# IMU_REV_D_1.net
KiCad netlist of a schematic drawn in Altium Designer
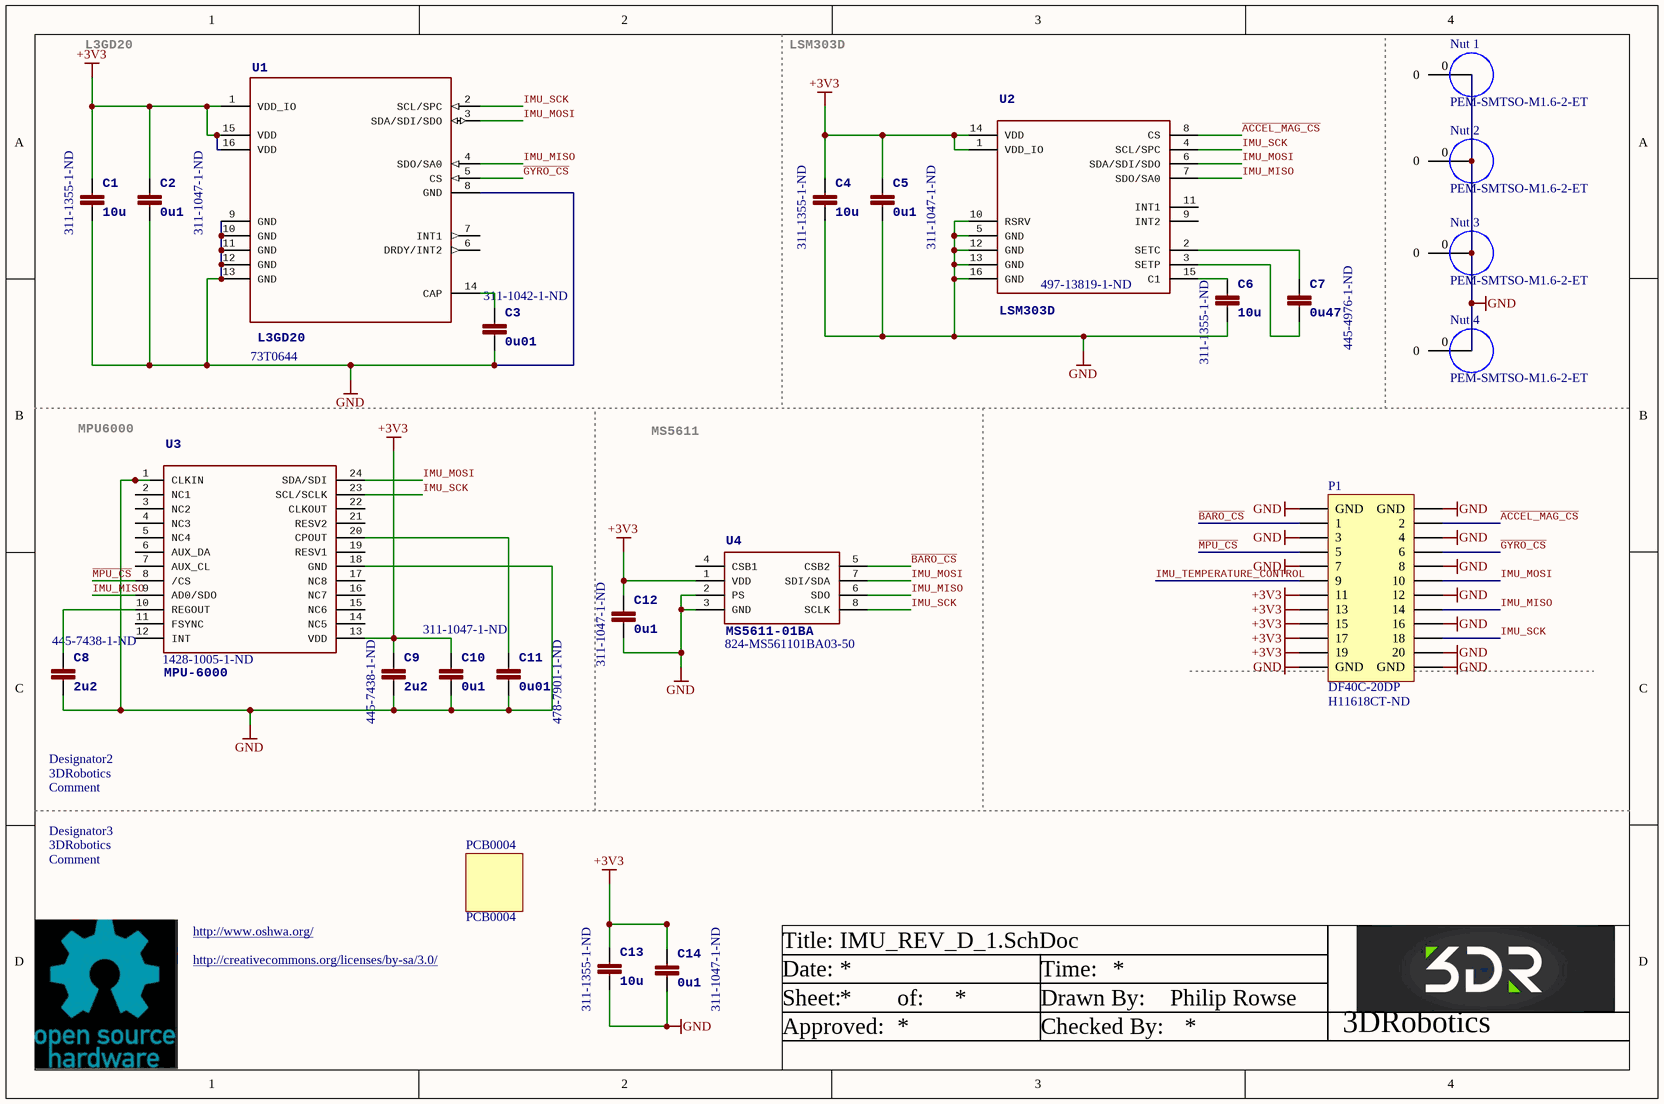
[diagram p0: IMU_REV_D_1.SchDoc]

(export (version "E")
  (design (tool "Eeschema 10.0.6"))
  (components
    (comp (ref "C1")
      (value "10u")
      (footprint "0805-CAP")
      (description "Capacitor, 10uF, 10V, Y5V, 0805, Ceramic")
      (fields
        (field (name "PARTNO") "CC0805ZKY5V6BB106")
        (field (name "SUPPLIER PART NUMBER 1") "311-1355-1-ND")
        (field (name "3DR_PARTNO") "ECM0713")
      )
      (libsource (lib "lib_pixhawk") (part "CAPACITOR-0805"))
    )
    (comp (ref "C2")
      (value "0u1")
      (footprint "0402-CAP")
      (description "Capacitor, 0.1uF, 16V, Y5V, 0402, Ceramic")
      (fields
        (field (name "PARTNO") "CC0402ZRY5V7BB104")
        (field (name "SUPPLIER PART NUMBER 1") "311-1047-1-ND")
        (field (name "3DR_PARTNO") "ECM0700")
      )
      (libsource (lib "lib_pixhawk") (part "CAPACITOR-0402"))
    )
    (comp (ref "C3")
      (value "0u01")
      (footprint "0402-CAP")
      (description "Capacitor, 10000pF, 16V, 10%, X7R, 0402, Ceramic")
      (fields
        (field (name "PARTNO") "CC0402KRX7R7BB103")
        (field (name "SUPPLIER PART NUMBER 1") "311-1042-1-ND")
        (field (name "3DR_PARTNO") "ECM0711")
      )
      (libsource (lib "lib_pixhawk") (part "CAPACITOR-0402"))
    )
    (comp (ref "C4")
      (value "10u")
      (footprint "0805-CAP")
      (description "Capacitor, 10uF, 10V, Y5V, 0805, Ceramic")
      (fields
        (field (name "PARTNO") "CC0805ZKY5V6BB106")
        (field (name "SUPPLIER PART NUMBER 1") "311-1355-1-ND")
        (field (name "3DR_PARTNO") "ECM0713")
      )
      (libsource (lib "lib_pixhawk") (part "CAPACITOR-0805"))
    )
    (comp (ref "C5")
      (value "0u1")
      (footprint "0402-CAP")
      (description "Capacitor, 0.1uF, 16V, Y5V, 0402, Ceramic")
      (fields
        (field (name "PARTNO") "CC0402ZRY5V7BB104")
        (field (name "SUPPLIER PART NUMBER 1") "311-1047-1-ND")
        (field (name "3DR_PARTNO") "ECM0700")
      )
      (libsource (lib "lib_pixhawk") (part "CAPACITOR-0402"))
    )
    (comp (ref "C6")
      (value "10u")
      (footprint "0805-CAP")
      (description "Capacitor, 10uF, 10V, Y5V, 0805, Ceramic")
      (fields
        (field (name "PARTNO") "CC0805ZKY5V6BB106")
        (field (name "SUPPLIER PART NUMBER 1") "311-1355-1-ND")
        (field (name "3DR_PARTNO") "ECM0713")
      )
      (libsource (lib "lib_pixhawk") (part "CAPACITOR-0805"))
    )
    (comp (ref "C7")
      (value "0u47")
      (footprint "0402-CAP")
      (description "Capacitor,  0.47uF, 16V, 10%, X5R, 0402, Ceramic")
      (fields
        (field (name "PARTNO") "C1005X5R1C474K050BC")
        (field (name "SUPPLIER PART NUMBER 1") "445-4976-1-ND")
        (field (name "3DR_PARTNO") "ECM0704")
      )
      (libsource (lib "lib_pixhawk") (part "CAPACITOR-0402"))
    )
    (comp (ref "C8")
      (value "2u2")
      (footprint "0603-CAP")
      (description "Capacitor, 2.2uF, 16V, 10%, X6S, 0603, Ceramic")
      (fields
        (field (name "PARTNO") "C1608X6S1C225K080AC")
        (field (name "SUPPLIER PART NUMBER 1") "445-7438-1-ND")
        (field (name "3DR_PARTNO") "ECM0619")
      )
      (libsource (lib "lib_pixhawk") (part "CAPACITOR-0603"))
    )
    (comp (ref "C9")
      (value "2u2")
      (footprint "0603-CAP")
      (description "Capacitor, 2.2uF, 16V, 10%, X6S, 0603, Ceramic")
      (fields
        (field (name "PARTNO") "C1608X6S1C225K080AC")
        (field (name "SUPPLIER PART NUMBER 1") "445-7438-1-ND")
        (field (name "3DR_PARTNO") "ECM0619")
      )
      (libsource (lib "lib_pixhawk") (part "CAPACITOR-0603"))
    )
    (comp (ref "C10")
      (value "0u1")
      (footprint "0402-CAP")
      (description "Capacitor, 0.1uF, 16V, Y5V, 0402, Ceramic")
      (fields
        (field (name "PARTNO") "CC0402ZRY5V7BB104")
        (field (name "SUPPLIER PART NUMBER 1") "311-1047-1-ND")
        (field (name "3DR_PARTNO") "ECM0700")
      )
      (libsource (lib "lib_pixhawk") (part "CAPACITOR-0402"))
    )
    (comp (ref "C11")
      (value "0u01")
      (footprint "0603-CAP")
      (description "Capacitor, 10000pF, 25V, 5%, X7R, 0603, Ceramic")
      (fields
        (field (name "PARTNO") "06033C103JAT2A")
        (field (name "SUPPLIER PART NUMBER 1") "478-7901-1-ND")
        (field (name "3DR_PARTNO") "ECM0620")
      )
      (libsource (lib "lib_pixhawk") (part "CAPACITOR-0603"))
    )
    (comp (ref "C12")
      (value "0u1")
      (footprint "0402-CAP")
      (description "Capacitor, 0.1uF, 16V, Y5V, 0402, Ceramic")
      (fields
        (field (name "PARTNO") "CC0402ZRY5V7BB104")
        (field (name "SUPPLIER PART NUMBER 1") "311-1047-1-ND")
        (field (name "3DR_PARTNO") "ECM0700")
      )
      (libsource (lib "lib_pixhawk") (part "CAPACITOR-0402"))
    )
    (comp (ref "C13")
      (value "10u")
      (footprint "0805-CAP")
      (description "Capacitor, 10uF, 10V, Y5V, 0805, Ceramic")
      (fields
        (field (name "PARTNO") "CC0805ZKY5V6BB106")
        (field (name "SUPPLIER PART NUMBER 1") "311-1355-1-ND")
        (field (name "3DR_PARTNO") "ECM0713")
      )
      (libsource (lib "lib_pixhawk") (part "CAPACITOR-0805"))
    )
    (comp (ref "C14")
      (value "0u1")
      (footprint "0402-CAP")
      (description "Capacitor, 0.1uF, 16V, Y5V, 0402, Ceramic")
      (fields
        (field (name "PARTNO") "CC0402ZRY5V7BB104")
        (field (name "SUPPLIER PART NUMBER 1") "311-1047-1-ND")
        (field (name "3DR_PARTNO") "ECM0700")
      )
      (libsource (lib "lib_pixhawk") (part "CAPACITOR-0402"))
    )
    (comp (ref "Designator2")
      (value "Comment")
      (footprint "3DR_SMALL")
      (fields (field (name "PARTNO") "DO NOT FIT"))
      (libsource (lib "lib_pixhawk") (part "3DR-Logo Large"))
    )
    (comp (ref "Designator3")
      (value "Comment")
      (footprint "3DR_SMALL")
      (fields (field (name "PARTNO") "DO NOT FIT"))
      (libsource (lib "lib_pixhawk") (part "3DR-Logo Large"))
    )
    (comp (ref "Nut 1")
      (value "PEM-SMTSO-M1.6-2-ET")
      (footprint "PEM-SMTSO-M1.6-2-ET")
      (description "Fastener, M1.6x2mm, SMTSO, Carbon Steel")
      (fields (field (name "3DR_PARTNO") "PRT0438"))
      (libsource (lib "pixhawk2") (part "PEM-SMTSO-M1.6-2-ET"))
    )
    (comp (ref "Nut 2")
      (value "PEM-SMTSO-M1.6-2-ET")
      (footprint "PEM-SMTSO-M1.6-2-ET")
      (description "Fastener, M1.6x2mm, SMTSO, Carbon Steel")
      (fields (field (name "3DR_PARTNO") "PRT0438"))
      (libsource (lib "pixhawk2") (part "PEM-SMTSO-M1.6-2-ET"))
    )
    (comp (ref "Nut 3")
      (value "PEM-SMTSO-M1.6-2-ET")
      (footprint "PEM-SMTSO-M1.6-2-ET")
      (description "Fastener, M1.6x2mm, SMTSO, Carbon Steel")
      (fields (field (name "3DR_PARTNO") "PRT0438"))
      (libsource (lib "pixhawk2") (part "PEM-SMTSO-M1.6-2-ET"))
    )
    (comp (ref "Nut 4")
      (value "PEM-SMTSO-M1.6-2-ET")
      (footprint "PEM-SMTSO-M1.6-2-ET")
      (description "Fastener, M1.6x2mm, SMTSO, Carbon Steel")
      (fields (field (name "3DR_PARTNO") "PRT0438"))
      (libsource (lib "pixhawk2") (part "PEM-SMTSO-M1.6-2-ET"))
    )
    (comp (ref "P1")
      (value "DF40C-20DP")
      (footprint "DF40C-20-DP")
      (description "Connector, HDR, 20Pos, 0.4mm, SMD, GOLD")
      (fields
        (field (name "SUPPLIER PART NUMBER 1") "H11618CT-ND")
        (field (name "3DR_PARTNO") "ECM0510")
        (field (name "PUBLISHER") "Altium Limited")
      )
      (libsource (lib "pixhawk2") (part "DF40C-20DP"))
    )
    (comp (ref "PCB0004")
      (value "PCB0004")
      (description "IMU PCB")
      (libsource (lib "lib_pixhawk") (part "PCB_0004"))
    )
    (comp (ref "U1")
      (value "L3GD20")
      (footprint "L3GD20")
      (description "Sensor, Low-power, Three-axis, Angular rate")
      (fields (field (name "SUPPLIER PART NUMBER 1") "73T0644") (field (name "3DR_PARTNO") "ECM0827"))
      (libsource (lib "pixhawk2") (part "L3GD20"))
    )
    (comp (ref "U2")
      (value "LSM303D")
      (footprint "LSM303D")
      (description "Module, 3D Accelerometer, 3D Magnetometer")
      (fields (field (name "SUPPLIER PART NUMBER 1") "497-13819-1-ND") (field (name "3DR_PARTNO") "ECM0828"))
      (libsource (lib "pixhawk2") (part "LSM303D"))
    )
    (comp (ref "U3")
      (value "MPU-6000")
      (footprint "QFN-24")
      (description "3 Axis Accel, 3Axis Gyro")
      (fields (field (name "SUPPLIER PART NUMBER 1") "1428-1005-1-ND") (field (name "3DR_PARTNO") "ECM0834"))
      (libsource (lib "pixhawk2") (part "MPU-6000"))
    )
    (comp (ref "U4")
      (value "MS5611-01BA")
      (footprint "MS5611-01BA")
      (description "Board, Digital pressure sensor I2C/SPI")
      (fields
        (field (name "SUPPLIER PART NUMBER 1") "824-MS561101BA03-50")
        (field (name "3DR_PARTNO") "ECM0835")
      )
      (libsource (lib "pixhawk2") (part "MS5611-01BA"))
    )
  )
  (nets
    (net (code "1") (name "+3V3") (class "Default")
      (node (ref "C1") (pin "P$1") (pinfunction "1_P$1") (pintype "passive"))
      (node (ref "C10") (pin "P$1") (pinfunction "1_P$1") (pintype "passive"))
      (node (ref "C12") (pin "P$1") (pinfunction "1_P$1") (pintype "passive"))
      (node (ref "C13") (pin "P$1") (pinfunction "1_P$1") (pintype "passive"))
      (node (ref "C14") (pin "P$1") (pinfunction "1_P$1") (pintype "passive"))
      (node (ref "C2") (pin "P$1") (pinfunction "1_P$1") (pintype "passive"))
      (node (ref "C4") (pin "P$1") (pinfunction "1_P$1") (pintype "passive"))
      (node (ref "C5") (pin "P$1") (pinfunction "1_P$1") (pintype "passive"))
      (node (ref "C9") (pin "P$1") (pinfunction "1_P$1") (pintype "passive"))
      (node (ref "P1") (pin "11") (pinfunction "11_11") (pintype "passive"))
      (node (ref "P1") (pin "13") (pinfunction "13_13") (pintype "passive"))
      (node (ref "P1") (pin "15") (pinfunction "15_15") (pintype "passive"))
      (node (ref "P1") (pin "17") (pinfunction "17_17") (pintype "passive"))
      (node (ref "P1") (pin "19") (pinfunction "19_19") (pintype "passive"))
      (node (ref "U1") (pin "1") (pinfunction "VDD_IO_1") (pintype "power_in"))
      (node (ref "U1") (pin "15") (pinfunction "VDD_15") (pintype "power_in"))
      (node (ref "U1") (pin "16") (pinfunction "VDD_16") (pintype "power_in"))
      (node (ref "U2") (pin "1") (pinfunction "VDD_IO_1") (pintype "passive"))
      (node (ref "U2") (pin "14") (pinfunction "VDD_14") (pintype "passive"))
      (node (ref "U3") (pin "13") (pinfunction "VDD_13") (pintype "passive"))
      (node (ref "U4") (pin "1") (pinfunction "VDD_1") (pintype "passive"))
    )
    (net (code "2") (name "/IMU_MISO") (class "Default")
      (node (ref "P1") (pin "14") (pinfunction "14_14") (pintype "passive"))
      (node (ref "U1") (pin "4") (pinfunction "SDO/SA0_4") (pintype "input"))
      (node (ref "U2") (pin "7") (pinfunction "SDO/SA0_7") (pintype "passive"))
      (node (ref "U3") (pin "9") (pinfunction "AD0/SDO_9") (pintype "passive"))
      (node (ref "U4") (pin "6") (pinfunction "SDO_6") (pintype "passive"))
    )
    (net (code "3") (name "/IMU_MOSI") (class "Default")
      (node (ref "P1") (pin "10") (pinfunction "10_10") (pintype "passive"))
      (node (ref "U1") (pin "3") (pinfunction "SDA/SDI/SDO_3") (pintype "bidirectional"))
      (node (ref "U2") (pin "6") (pinfunction "SDA/SDI/SDO_6") (pintype "passive"))
      (node (ref "U3") (pin "24") (pinfunction "SDA/SDI_24") (pintype "passive"))
      (node (ref "U4") (pin "7") (pinfunction "SDI/SDA_7") (pintype "passive"))
    )
    (net (code "4") (name "/IMU_SCK") (class "Default")
      (node (ref "P1") (pin "18") (pinfunction "18_18") (pintype "passive"))
      (node (ref "U1") (pin "2") (pinfunction "SCL/SPC_2") (pintype "input"))
      (node (ref "U2") (pin "4") (pinfunction "SCL/SPC_4") (pintype "passive"))
      (node (ref "U3") (pin "23") (pinfunction "SCL/SCLK_23") (pintype "passive"))
      (node (ref "U4") (pin "8") (pinfunction "SCLK_8") (pintype "passive"))
    )
    (net (code "5") (name "/IMU_TEMPERATURE_CONTROL") (class "Default")
      (node (ref "P1") (pin "9") (pinfunction "9_9") (pintype "passive"))
    )
    (net (code "6") (name "/~{ACCEL_MAG_CS}") (class "Default")
      (node (ref "P1") (pin "2") (pinfunction "2_2") (pintype "passive"))
      (node (ref "U2") (pin "8") (pinfunction "CS_8") (pintype "passive"))
    )
    (net (code "7") (name "/~{BARO_CS}") (class "Default")
      (node (ref "P1") (pin "1") (pinfunction "1_1") (pintype "passive"))
      (node (ref "U4") (pin "5") (pinfunction "CSB2_5") (pintype "passive"))
    )
    (net (code "8") (name "/~{GYRO_CS}") (class "Default")
      (node (ref "P1") (pin "6") (pinfunction "6_6") (pintype "passive"))
      (node (ref "U1") (pin "5") (pinfunction "CS_5") (pintype "input"))
    )
    (net (code "9") (name "/~{MPU_CS}") (class "Default")
      (node (ref "P1") (pin "5") (pinfunction "5_5") (pintype "passive"))
      (node (ref "U3") (pin "8") (pinfunction "/CS_8") (pintype "passive"))
    )
    (net (code "10") (name "GND") (class "Default")
      (node (ref "C1") (pin "P$2") (pinfunction "2_P$2") (pintype "passive"))
      (node (ref "C10") (pin "P$2") (pinfunction "2_P$2") (pintype "passive"))
      (node (ref "C11") (pin "P$2") (pinfunction "2_P$2") (pintype "passive"))
      (node (ref "C12") (pin "P$2") (pinfunction "2_P$2") (pintype "passive"))
      (node (ref "C13") (pin "P$2") (pinfunction "2_P$2") (pintype "passive"))
      (node (ref "C14") (pin "P$2") (pinfunction "2_P$2") (pintype "passive"))
      (node (ref "C2") (pin "P$2") (pinfunction "2_P$2") (pintype "passive"))
      (node (ref "C3") (pin "P$2") (pinfunction "2_P$2") (pintype "passive"))
      (node (ref "C4") (pin "P$2") (pinfunction "2_P$2") (pintype "passive"))
      (node (ref "C5") (pin "P$2") (pinfunction "2_P$2") (pintype "passive"))
      (node (ref "C6") (pin "P$2") (pinfunction "2_P$2") (pintype "passive"))
      (node (ref "C8") (pin "P$2") (pinfunction "2_P$2") (pintype "passive"))
      (node (ref "C9") (pin "P$2") (pinfunction "2_P$2") (pintype "passive"))
      (node (ref "Nut 1") (pin "0") (pinfunction "0_0") (pintype "passive"))
      (node (ref "Nut 2") (pin "0") (pinfunction "0_0") (pintype "passive"))
      (node (ref "Nut 3") (pin "0") (pinfunction "0_0") (pintype "passive"))
      (node (ref "Nut 4") (pin "0") (pinfunction "0_0") (pintype "passive"))
      (node (ref "P1") (pin "12") (pinfunction "12_12") (pintype "passive"))
      (node (ref "P1") (pin "16") (pinfunction "16_16") (pintype "passive"))
      (node (ref "P1") (pin "20") (pinfunction "20_20") (pintype "passive"))
      (node (ref "P1") (pin "21") (pinfunction "GND_21") (pintype "passive"))
      (node (ref "P1") (pin "22") (pinfunction "GND_22") (pintype "passive"))
      (node (ref "P1") (pin "23") (pinfunction "GND_23") (pintype "passive"))
      (node (ref "P1") (pin "24") (pinfunction "GND_24") (pintype "passive"))
      (node (ref "P1") (pin "3") (pinfunction "3_3") (pintype "passive"))
      (node (ref "P1") (pin "4") (pinfunction "4_4") (pintype "passive"))
      (node (ref "P1") (pin "7") (pinfunction "7_7") (pintype "passive"))
      (node (ref "P1") (pin "8") (pinfunction "8_8") (pintype "passive"))
      (node (ref "U1") (pin "10") (pinfunction "GND_10") (pintype "power_in"))
      (node (ref "U1") (pin "11") (pinfunction "GND_11") (pintype "power_in"))
      (node (ref "U1") (pin "12") (pinfunction "GND_12") (pintype "power_in"))
      (node (ref "U1") (pin "13") (pinfunction "GND_13") (pintype "power_in"))
      (node (ref "U1") (pin "8") (pinfunction "GND_8") (pintype "power_in"))
      (node (ref "U1") (pin "9") (pinfunction "GND_9") (pintype "power_in"))
      (node (ref "U2") (pin "10") (pinfunction "RSRV_10") (pintype "passive"))
      (node (ref "U2") (pin "12") (pinfunction "GND_12") (pintype "passive"))
      (node (ref "U2") (pin "13") (pinfunction "GND_13") (pintype "passive"))
      (node (ref "U2") (pin "16") (pinfunction "GND_16") (pintype "passive"))
      (node (ref "U2") (pin "5") (pinfunction "GND_5") (pintype "passive"))
      (node (ref "U3") (pin "1") (pinfunction "CLKIN_1") (pintype "passive"))
      (node (ref "U3") (pin "18") (pinfunction "GND_18") (pintype "passive"))
      (node (ref "U4") (pin "2") (pinfunction "PS_2") (pintype "passive"))
      (node (ref "U4") (pin "3") (pinfunction "GND_3") (pintype "passive"))
    )
    (net (code "11") (name "Net-(C3-1)") (class "Default")
      (node (ref "C3") (pin "P$1") (pinfunction "1_P$1") (pintype "passive"))
      (node (ref "U1") (pin "14") (pinfunction "CAP_14") (pintype "passive"))
    )
    (net (code "12") (name "Net-(C6-1)") (class "Default")
      (node (ref "C6") (pin "P$1") (pinfunction "1_P$1") (pintype "passive"))
      (node (ref "U2") (pin "15") (pinfunction "C1_15") (pintype "passive"))
    )
    (net (code "13") (name "Net-(C7-1)") (class "Default")
      (node (ref "C7") (pin "P$1") (pinfunction "1_P$1") (pintype "passive"))
      (node (ref "U2") (pin "2") (pinfunction "SETC_2") (pintype "passive"))
    )
    (net (code "14") (name "Net-(C7-2)") (class "Default")
      (node (ref "C7") (pin "P$2") (pinfunction "2_P$2") (pintype "passive"))
      (node (ref "U2") (pin "3") (pinfunction "SETP_3") (pintype "passive"))
    )
    (net (code "15") (name "Net-(C8-1)") (class "Default")
      (node (ref "C8") (pin "P$1") (pinfunction "1_P$1") (pintype "passive"))
      (node (ref "U3") (pin "10") (pinfunction "REGOUT_10") (pintype "passive"))
    )
    (net (code "16") (name "Net-(C11-1)") (class "Default")
      (node (ref "C11") (pin "P$1") (pinfunction "1_P$1") (pintype "passive"))
      (node (ref "U3") (pin "20") (pinfunction "CPOUT_20") (pintype "passive"))
    )
    (net (code "17") (name "unconnected-(U1-DRDY{slash}INT2-Pad6)") (class "Default")
      (node (ref "U1") (pin "6") (pinfunction "DRDY/INT2_6") (pintype "output"))
    )
    (net (code "18") (name "unconnected-(U1-INT1-Pad7)") (class "Default")
      (node (ref "U1") (pin "7") (pinfunction "INT1_7") (pintype "output"))
    )
    (net (code "19") (name "unconnected-(U2-INT1-Pad11)") (class "Default")
      (node (ref "U2") (pin "11") (pinfunction "INT1_11") (pintype "passive"))
    )
    (net (code "20") (name "unconnected-(U2-INT2-Pad9)") (class "Default")
      (node (ref "U2") (pin "9") (pinfunction "INT2_9") (pintype "passive"))
    )
    (net (code "21") (name "unconnected-(U3-AUX_CL-Pad7)") (class "Default")
      (node (ref "U3") (pin "7") (pinfunction "AUX_CL_7") (pintype "passive"))
    )
    (net (code "22") (name "unconnected-(U3-AUX_DA-Pad6)") (class "Default")
      (node (ref "U3") (pin "6") (pinfunction "AUX_DA_6") (pintype "passive"))
    )
    (net (code "23") (name "unconnected-(U3-CLKOUT-Pad22)") (class "Default")
      (node (ref "U3") (pin "22") (pinfunction "CLKOUT_22") (pintype "passive"))
    )
    (net (code "24") (name "unconnected-(U3-FSYNC-Pad11)") (class "Default")
      (node (ref "U3") (pin "11") (pinfunction "FSYNC_11") (pintype "passive"))
    )
    (net (code "25") (name "unconnected-(U3-INT-Pad12)") (class "Default")
      (node (ref "U3") (pin "12") (pinfunction "INT_12") (pintype "passive"))
    )
    (net (code "26") (name "unconnected-(U3-NC1-Pad2)") (class "Default")
      (node (ref "U3") (pin "2") (pinfunction "NC1_2") (pintype "passive"))
    )
    (net (code "27") (name "unconnected-(U3-NC2-Pad3)") (class "Default")
      (node (ref "U3") (pin "3") (pinfunction "NC2_3") (pintype "passive"))
    )
    (net (code "28") (name "unconnected-(U3-NC3-Pad4)") (class "Default")
      (node (ref "U3") (pin "4") (pinfunction "NC3_4") (pintype "passive"))
    )
    (net (code "29") (name "unconnected-(U3-NC4-Pad5)") (class "Default")
      (node (ref "U3") (pin "5") (pinfunction "NC4_5") (pintype "passive"))
    )
    (net (code "30") (name "unconnected-(U3-NC5-Pad14)") (class "Default")
      (node (ref "U3") (pin "14") (pinfunction "NC5_14") (pintype "passive"))
    )
    (net (code "31") (name "unconnected-(U3-NC6-Pad15)") (class "Default")
      (node (ref "U3") (pin "15") (pinfunction "NC6_15") (pintype "passive"))
    )
    (net (code "32") (name "unconnected-(U3-NC7-Pad16)") (class "Default")
      (node (ref "U3") (pin "16") (pinfunction "NC7_16") (pintype "passive"))
    )
    (net (code "33") (name "unconnected-(U3-NC8-Pad17)") (class "Default")
      (node (ref "U3") (pin "17") (pinfunction "NC8_17") (pintype "passive"))
    )
    (net (code "34") (name "unconnected-(U3-RESV1-Pad19)") (class "Default")
      (node (ref "U3") (pin "19") (pinfunction "RESV1_19") (pintype "passive"))
    )
    (net (code "35") (name "unconnected-(U3-RESV2-Pad21)") (class "Default")
      (node (ref "U3") (pin "21") (pinfunction "RESV2_21") (pintype "passive"))
    )
    (net (code "36") (name "unconnected-(U4-CSB1-Pad4)") (class "Default")
      (node (ref "U4") (pin "4") (pinfunction "CSB1_4") (pintype "passive"))
    )
  )
)
